# motor.net
KiCad netlist of a schematic drawn in Altium Designer
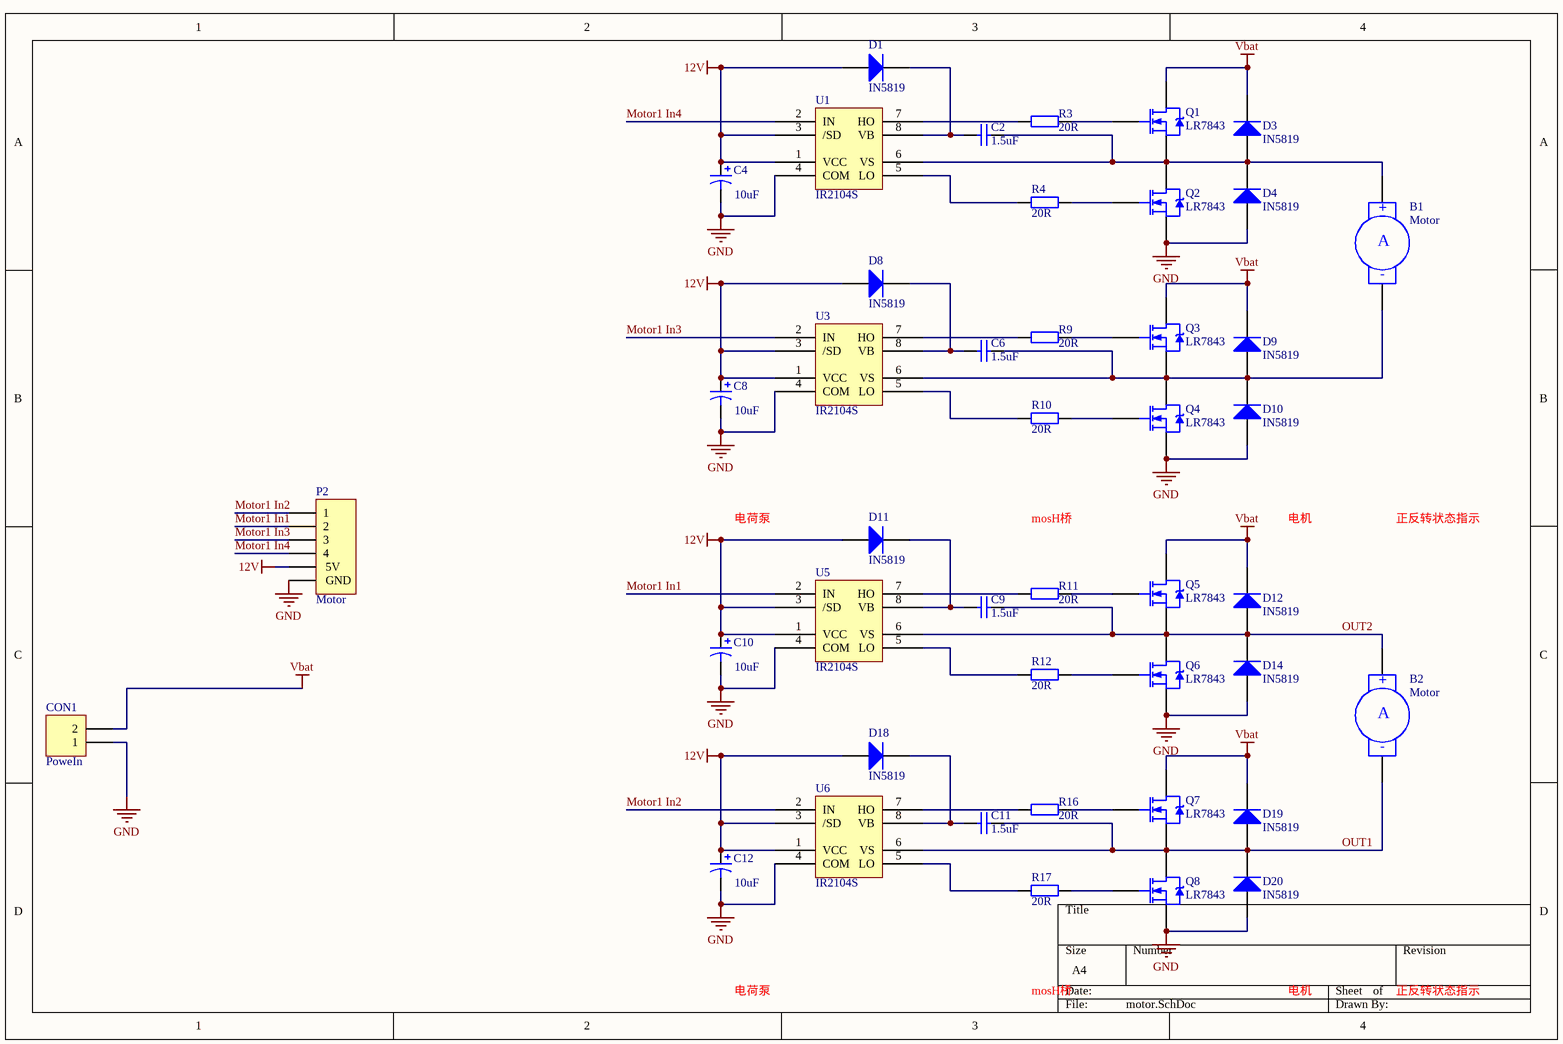
[diagram p0: motor.SchDoc]

(export (version "E")
  (design (tool "Eeschema 10.0.6"))
  (components
    (comp (ref "B1")
      (value "Motor")
      (footprint "KF301-2P")
      (description "Servo Motor")
      (fields (field (name "PUBLISHER") "Altium Limited"))
      (libsource (lib "Miscellaneous Devices") (part "Motor Servo"))
    )
    (comp (ref "B2")
      (value "Motor")
      (footprint "KF301-2P")
      (description "Servo Motor")
      (fields (field (name "PUBLISHER") "Altium Limited"))
      (libsource (lib "Miscellaneous Devices") (part "Motor Servo"))
    )
    (comp (ref "C2")
      (value "1.5uF")
      (footprint "0805(2012)")
      (description "Capacitor (Semiconductor SIM Model)")
      (fields (field (name "PUBLISHER") "Altium Limited"))
      (libsource (lib "Miscellaneous Devices") (part "Cap Semi"))
    )
    (comp (ref "C4")
      (value "10uF")
      (footprint "0805(2012)")
      (description "Polarized Capacitor (Surface Mount)")
      (fields (field (name "PUBLISHER") "Altium Limited"))
      (libsource (lib "Miscellaneous Devices") (part "Cap Pol3"))
    )
    (comp (ref "C6")
      (value "1.5uF")
      (footprint "0805(2012)")
      (description "Capacitor (Semiconductor SIM Model)")
      (fields (field (name "PUBLISHER") "Altium Limited"))
      (libsource (lib "Miscellaneous Devices") (part "Cap Semi"))
    )
    (comp (ref "C8")
      (value "10uF")
      (footprint "0805(2012)")
      (description "Polarized Capacitor (Surface Mount)")
      (fields (field (name "PUBLISHER") "Altium Limited"))
      (libsource (lib "Miscellaneous Devices") (part "Cap Pol3"))
    )
    (comp (ref "C9")
      (value "1.5uF")
      (footprint "0805(2012)")
      (description "Capacitor (Semiconductor SIM Model)")
      (fields (field (name "PUBLISHER") "Altium Limited"))
      (libsource (lib "Miscellaneous Devices") (part "Cap Semi"))
    )
    (comp (ref "C10")
      (value "10uF")
      (footprint "0805(2012)")
      (description "Polarized Capacitor (Surface Mount)")
      (fields (field (name "PUBLISHER") "Altium Limited"))
      (libsource (lib "Miscellaneous Devices") (part "Cap Pol3"))
    )
    (comp (ref "C11")
      (value "1.5uF")
      (footprint "0805(2012)")
      (description "Capacitor (Semiconductor SIM Model)")
      (fields (field (name "PUBLISHER") "Altium Limited"))
      (libsource (lib "Miscellaneous Devices") (part "Cap Semi"))
    )
    (comp (ref "C12")
      (value "10uF")
      (footprint "0805(2012)")
      (description "Polarized Capacitor (Surface Mount)")
      (fields (field (name "PUBLISHER") "Altium Limited"))
      (libsource (lib "Miscellaneous Devices") (part "Cap Pol3"))
    )
    (comp (ref "CON1")
      (value "PoweIn")
      (footprint "POWER")
      (description "Header, 2-Pin")
      (fields (field (name "PUBLISHER") "Altium Limited"))
      (libsource (lib "Miscellaneous Connectors") (part "Header 2"))
    )
    (comp (ref "D1")
      (value "IN5819")
      (footprint "1206(3216)")
      (description "Default Diode")
      (fields (field (name "PUBLISHER") "Altium Limited"))
      (libsource (lib "Miscellaneous Devices") (part "Diode"))
    )
    (comp (ref "D3")
      (value "IN5819")
      (footprint "1206(3216)")
      (description "Default Diode")
      (fields (field (name "PUBLISHER") "Altium Limited"))
      (libsource (lib "Miscellaneous Devices") (part "Diode"))
    )
    (comp (ref "D4")
      (value "IN5819")
      (footprint "1206(3216)")
      (description "Default Diode")
      (fields (field (name "PUBLISHER") "Altium Limited"))
      (libsource (lib "Miscellaneous Devices") (part "Diode"))
    )
    (comp (ref "D8")
      (value "IN5819")
      (footprint "1206(3216)")
      (description "Default Diode")
      (fields (field (name "PUBLISHER") "Altium Limited"))
      (libsource (lib "Miscellaneous Devices") (part "Diode"))
    )
    (comp (ref "D9")
      (value "IN5819")
      (footprint "1206(3216)")
      (description "Default Diode")
      (fields (field (name "PUBLISHER") "Altium Limited"))
      (libsource (lib "Miscellaneous Devices") (part "Diode"))
    )
    (comp (ref "D10")
      (value "IN5819")
      (footprint "1206(3216)")
      (description "Default Diode")
      (fields (field (name "PUBLISHER") "Altium Limited"))
      (libsource (lib "Miscellaneous Devices") (part "Diode"))
    )
    (comp (ref "D11")
      (value "IN5819")
      (footprint "1206(3216)")
      (description "Default Diode")
      (fields (field (name "PUBLISHER") "Altium Limited"))
      (libsource (lib "Miscellaneous Devices") (part "Diode"))
    )
    (comp (ref "D12")
      (value "IN5819")
      (footprint "1206(3216)")
      (description "Default Diode")
      (fields (field (name "PUBLISHER") "Altium Limited"))
      (libsource (lib "Miscellaneous Devices") (part "Diode"))
    )
    (comp (ref "D14")
      (value "IN5819")
      (footprint "1206(3216)")
      (description "Default Diode")
      (fields (field (name "PUBLISHER") "Altium Limited"))
      (libsource (lib "Miscellaneous Devices") (part "Diode"))
    )
    (comp (ref "D18")
      (value "IN5819")
      (footprint "1206(3216)")
      (description "Default Diode")
      (fields (field (name "PUBLISHER") "Altium Limited"))
      (libsource (lib "Miscellaneous Devices") (part "Diode"))
    )
    (comp (ref "D19")
      (value "IN5819")
      (footprint "1206(3216)")
      (description "Default Diode")
      (fields (field (name "PUBLISHER") "Altium Limited"))
      (libsource (lib "Miscellaneous Devices") (part "Diode"))
    )
    (comp (ref "D20")
      (value "IN5819")
      (footprint "1206(3216)")
      (description "Default Diode")
      (fields (field (name "PUBLISHER") "Altium Limited"))
      (libsource (lib "Miscellaneous Devices") (part "Diode"))
    )
    (comp (ref "P2") (value "Motor") (footprint "HDR1X6") (libsource (lib "主控板原理图") (part "Motor")))
    (comp (ref "Q1")
      (value "LR7843")
      (footprint "LR7843")
      (description "N-Channel Power MOSFET")
      (fields (field (name "PUBLISHER") "Altium Limited"))
      (libsource (lib "Miscellaneous Devices") (part "NMOS-2"))
    )
    (comp (ref "Q2")
      (value "LR7843")
      (footprint "LR7843")
      (description "N-Channel Power MOSFET")
      (fields (field (name "PUBLISHER") "Altium Limited"))
      (libsource (lib "Miscellaneous Devices") (part "NMOS-2"))
    )
    (comp (ref "Q3")
      (value "LR7843")
      (footprint "LR7843")
      (description "N-Channel Power MOSFET")
      (fields (field (name "PUBLISHER") "Altium Limited"))
      (libsource (lib "Miscellaneous Devices") (part "NMOS-2"))
    )
    (comp (ref "Q4")
      (value "LR7843")
      (footprint "LR7843")
      (description "N-Channel Power MOSFET")
      (fields (field (name "PUBLISHER") "Altium Limited"))
      (libsource (lib "Miscellaneous Devices") (part "NMOS-2"))
    )
    (comp (ref "Q5")
      (value "LR7843")
      (footprint "LR7843")
      (description "N-Channel Power MOSFET")
      (fields (field (name "PUBLISHER") "Altium Limited"))
      (libsource (lib "Miscellaneous Devices") (part "NMOS-2"))
    )
    (comp (ref "Q6")
      (value "LR7843")
      (footprint "LR7843")
      (description "N-Channel Power MOSFET")
      (fields (field (name "PUBLISHER") "Altium Limited"))
      (libsource (lib "Miscellaneous Devices") (part "NMOS-2"))
    )
    (comp (ref "Q7")
      (value "LR7843")
      (footprint "LR7843")
      (description "N-Channel Power MOSFET")
      (fields (field (name "PUBLISHER") "Altium Limited"))
      (libsource (lib "Miscellaneous Devices") (part "NMOS-2"))
    )
    (comp (ref "Q8")
      (value "LR7843")
      (footprint "LR7843")
      (description "N-Channel Power MOSFET")
      (fields (field (name "PUBLISHER") "Altium Limited"))
      (libsource (lib "Miscellaneous Devices") (part "NMOS-2"))
    )
    (comp (ref "R3")
      (value "20R")
      (footprint "0603")
      (description "Resistor")
      (fields (field (name "PUBLISHER") "Altium Limited"))
      (libsource (lib "Miscellaneous Devices") (part "Res2"))
    )
    (comp (ref "R4")
      (value "20R")
      (footprint "0603")
      (description "Resistor")
      (fields (field (name "PUBLISHER") "Altium Limited"))
      (libsource (lib "Miscellaneous Devices") (part "Res2"))
    )
    (comp (ref "R9")
      (value "20R")
      (footprint "0603")
      (description "Resistor")
      (fields (field (name "PUBLISHER") "Altium Limited"))
      (libsource (lib "Miscellaneous Devices") (part "Res2"))
    )
    (comp (ref "R10")
      (value "20R")
      (footprint "0603")
      (description "Resistor")
      (fields (field (name "PUBLISHER") "Altium Limited"))
      (libsource (lib "Miscellaneous Devices") (part "Res2"))
    )
    (comp (ref "R11")
      (value "20R")
      (footprint "0603")
      (description "Resistor")
      (fields (field (name "PUBLISHER") "Altium Limited"))
      (libsource (lib "Miscellaneous Devices") (part "Res2"))
    )
    (comp (ref "R12")
      (value "20R")
      (footprint "0603")
      (description "Resistor")
      (fields (field (name "PUBLISHER") "Altium Limited"))
      (libsource (lib "Miscellaneous Devices") (part "Res2"))
    )
    (comp (ref "R16")
      (value "20R")
      (footprint "0603")
      (description "Resistor")
      (fields (field (name "PUBLISHER") "Altium Limited"))
      (libsource (lib "Miscellaneous Devices") (part "Res2"))
    )
    (comp (ref "R17")
      (value "20R")
      (footprint "0603")
      (description "Resistor")
      (fields (field (name "PUBLISHER") "Altium Limited"))
      (libsource (lib "Miscellaneous Devices") (part "Res2"))
    )
    (comp (ref "U1") (value "IR2104S") (footprint "IR2104S") (libsource (lib "LY") (part "IR2104S")))
    (comp (ref "U3") (value "IR2104S") (footprint "IR2104S") (libsource (lib "LY") (part "IR2104S")))
    (comp (ref "U5") (value "IR2104S") (footprint "IR2104S") (libsource (lib "LY") (part "IR2104S")))
    (comp (ref "U6") (value "IR2104S") (footprint "IR2104S") (libsource (lib "LY") (part "IR2104S")))
  )
  (nets
    (net (code "1") (name "/Motor1 In1") (class "Default")
      (node (ref "P2") (pin "2") (pinfunction "2_2") (pintype "passive"))
      (node (ref "U5") (pin "2") (pinfunction "IN_2") (pintype "passive"))
    )
    (net (code "2") (name "/Motor1 In2") (class "Default")
      (node (ref "P2") (pin "1") (pinfunction "1_1") (pintype "passive"))
      (node (ref "U6") (pin "2") (pinfunction "IN_2") (pintype "passive"))
    )
    (net (code "3") (name "/Motor1 In3") (class "Default")
      (node (ref "P2") (pin "3") (pinfunction "3_3") (pintype "passive"))
      (node (ref "U3") (pin "2") (pinfunction "IN_2") (pintype "passive"))
    )
    (net (code "4") (name "/Motor1 In4") (class "Default")
      (node (ref "P2") (pin "4") (pinfunction "4_4") (pintype "passive"))
      (node (ref "U1") (pin "2") (pinfunction "IN_2") (pintype "passive"))
    )
    (net (code "5") (name "/OUT1") (class "Default")
      (node (ref "B2") (pin "2") (pinfunction "-_2") (pintype "passive"))
      (node (ref "C11") (pin "2") (pinfunction "2_2") (pintype "passive"))
      (node (ref "D19") (pin "1") (pinfunction "A_1") (pintype "passive"))
      (node (ref "D20") (pin "2") (pinfunction "K_2") (pintype "passive"))
      (node (ref "Q7") (pin "3") (pinfunction "S_3") (pintype "passive"))
      (node (ref "Q8") (pin "2") (pinfunction "D_2") (pintype "passive"))
      (node (ref "U6") (pin "6") (pinfunction "VS_6") (pintype "passive"))
    )
    (net (code "6") (name "/OUT2") (class "Default")
      (node (ref "B2") (pin "1") (pinfunction "+_1") (pintype "passive"))
      (node (ref "C9") (pin "2") (pinfunction "2_2") (pintype "passive"))
      (node (ref "D12") (pin "1") (pinfunction "A_1") (pintype "passive"))
      (node (ref "D14") (pin "2") (pinfunction "K_2") (pintype "passive"))
      (node (ref "Q5") (pin "3") (pinfunction "S_3") (pintype "passive"))
      (node (ref "Q6") (pin "2") (pinfunction "D_2") (pintype "passive"))
      (node (ref "U5") (pin "6") (pinfunction "VS_6") (pintype "passive"))
    )
    (net (code "7") (name "12V") (class "Default")
      (node (ref "C10") (pin "1") (pinfunction "1_1") (pintype "passive"))
      (node (ref "C12") (pin "1") (pinfunction "1_1") (pintype "passive"))
      (node (ref "C4") (pin "1") (pinfunction "1_1") (pintype "passive"))
      (node (ref "C8") (pin "1") (pinfunction "1_1") (pintype "passive"))
      (node (ref "D1") (pin "1") (pinfunction "A_1") (pintype "passive"))
      (node (ref "D11") (pin "1") (pinfunction "A_1") (pintype "passive"))
      (node (ref "D18") (pin "1") (pinfunction "A_1") (pintype "passive"))
      (node (ref "D8") (pin "1") (pinfunction "A_1") (pintype "passive"))
      (node (ref "P2") (pin "5") (pinfunction "5V_5") (pintype "passive"))
      (node (ref "U1") (pin "1") (pinfunction "VCC_1") (pintype "passive"))
      (node (ref "U1") (pin "3") (pinfunction "/SD_3") (pintype "passive"))
      (node (ref "U3") (pin "1") (pinfunction "VCC_1") (pintype "passive"))
      (node (ref "U3") (pin "3") (pinfunction "/SD_3") (pintype "passive"))
      (node (ref "U5") (pin "1") (pinfunction "VCC_1") (pintype "passive"))
      (node (ref "U5") (pin "3") (pinfunction "/SD_3") (pintype "passive"))
      (node (ref "U6") (pin "1") (pinfunction "VCC_1") (pintype "passive"))
      (node (ref "U6") (pin "3") (pinfunction "/SD_3") (pintype "passive"))
    )
    (net (code "8") (name "GND") (class "Default")
      (node (ref "C10") (pin "2") (pinfunction "2_2") (pintype "passive"))
      (node (ref "C12") (pin "2") (pinfunction "2_2") (pintype "passive"))
      (node (ref "C4") (pin "2") (pinfunction "2_2") (pintype "passive"))
      (node (ref "C8") (pin "2") (pinfunction "2_2") (pintype "passive"))
      (node (ref "CON1") (pin "1") (pinfunction "1_1") (pintype "passive"))
      (node (ref "D10") (pin "1") (pinfunction "A_1") (pintype "passive"))
      (node (ref "D14") (pin "1") (pinfunction "A_1") (pintype "passive"))
      (node (ref "D20") (pin "1") (pinfunction "A_1") (pintype "passive"))
      (node (ref "D4") (pin "1") (pinfunction "A_1") (pintype "passive"))
      (node (ref "P2") (pin "6") (pinfunction "GND_6") (pintype "passive"))
      (node (ref "Q2") (pin "3") (pinfunction "S_3") (pintype "passive"))
      (node (ref "Q4") (pin "3") (pinfunction "S_3") (pintype "passive"))
      (node (ref "Q6") (pin "3") (pinfunction "S_3") (pintype "passive"))
      (node (ref "Q8") (pin "3") (pinfunction "S_3") (pintype "passive"))
      (node (ref "U1") (pin "4") (pinfunction "COM_4") (pintype "passive"))
      (node (ref "U3") (pin "4") (pinfunction "COM_4") (pintype "passive"))
      (node (ref "U5") (pin "4") (pinfunction "COM_4") (pintype "passive"))
      (node (ref "U6") (pin "4") (pinfunction "COM_4") (pintype "passive"))
    )
    (net (code "9") (name "Net-(B1-+)") (class "Default")
      (node (ref "B1") (pin "1") (pinfunction "+_1") (pintype "passive"))
      (node (ref "C2") (pin "2") (pinfunction "2_2") (pintype "passive"))
      (node (ref "D3") (pin "1") (pinfunction "A_1") (pintype "passive"))
      (node (ref "D4") (pin "2") (pinfunction "K_2") (pintype "passive"))
      (node (ref "Q1") (pin "3") (pinfunction "S_3") (pintype "passive"))
      (node (ref "Q2") (pin "2") (pinfunction "D_2") (pintype "passive"))
      (node (ref "U1") (pin "6") (pinfunction "VS_6") (pintype "passive"))
    )
    (net (code "10") (name "Net-(B1--)") (class "Default")
      (node (ref "B1") (pin "2") (pinfunction "-_2") (pintype "passive"))
      (node (ref "C6") (pin "2") (pinfunction "2_2") (pintype "passive"))
      (node (ref "D10") (pin "2") (pinfunction "K_2") (pintype "passive"))
      (node (ref "D9") (pin "1") (pinfunction "A_1") (pintype "passive"))
      (node (ref "Q3") (pin "3") (pinfunction "S_3") (pintype "passive"))
      (node (ref "Q4") (pin "2") (pinfunction "D_2") (pintype "passive"))
      (node (ref "U3") (pin "6") (pinfunction "VS_6") (pintype "passive"))
    )
    (net (code "11") (name "Net-(D1-K)") (class "Default")
      (node (ref "C2") (pin "1") (pinfunction "1_1") (pintype "passive"))
      (node (ref "D1") (pin "2") (pinfunction "K_2") (pintype "passive"))
      (node (ref "U1") (pin "8") (pinfunction "VB_8") (pintype "passive"))
    )
    (net (code "12") (name "Net-(D8-K)") (class "Default")
      (node (ref "C6") (pin "1") (pinfunction "1_1") (pintype "passive"))
      (node (ref "D8") (pin "2") (pinfunction "K_2") (pintype "passive"))
      (node (ref "U3") (pin "8") (pinfunction "VB_8") (pintype "passive"))
    )
    (net (code "13") (name "Net-(D11-K)") (class "Default")
      (node (ref "C9") (pin "1") (pinfunction "1_1") (pintype "passive"))
      (node (ref "D11") (pin "2") (pinfunction "K_2") (pintype "passive"))
      (node (ref "U5") (pin "8") (pinfunction "VB_8") (pintype "passive"))
    )
    (net (code "14") (name "Net-(D18-K)") (class "Default")
      (node (ref "C11") (pin "1") (pinfunction "1_1") (pintype "passive"))
      (node (ref "D18") (pin "2") (pinfunction "K_2") (pintype "passive"))
      (node (ref "U6") (pin "8") (pinfunction "VB_8") (pintype "passive"))
    )
    (net (code "15") (name "Net-(Q1-G)") (class "Default")
      (node (ref "Q1") (pin "1") (pinfunction "G_1") (pintype "passive"))
      (node (ref "R3") (pin "2") (pinfunction "2_2") (pintype "passive"))
    )
    (net (code "16") (name "Net-(Q2-G)") (class "Default")
      (node (ref "Q2") (pin "1") (pinfunction "G_1") (pintype "passive"))
      (node (ref "R4") (pin "2") (pinfunction "2_2") (pintype "passive"))
    )
    (net (code "17") (name "Net-(Q3-G)") (class "Default")
      (node (ref "Q3") (pin "1") (pinfunction "G_1") (pintype "passive"))
      (node (ref "R9") (pin "2") (pinfunction "2_2") (pintype "passive"))
    )
    (net (code "18") (name "Net-(Q4-G)") (class "Default")
      (node (ref "Q4") (pin "1") (pinfunction "G_1") (pintype "passive"))
      (node (ref "R10") (pin "2") (pinfunction "2_2") (pintype "passive"))
    )
    (net (code "19") (name "Net-(Q5-G)") (class "Default")
      (node (ref "Q5") (pin "1") (pinfunction "G_1") (pintype "passive"))
      (node (ref "R11") (pin "2") (pinfunction "2_2") (pintype "passive"))
    )
    (net (code "20") (name "Net-(Q6-G)") (class "Default")
      (node (ref "Q6") (pin "1") (pinfunction "G_1") (pintype "passive"))
      (node (ref "R12") (pin "2") (pinfunction "2_2") (pintype "passive"))
    )
    (net (code "21") (name "Net-(Q7-G)") (class "Default")
      (node (ref "Q7") (pin "1") (pinfunction "G_1") (pintype "passive"))
      (node (ref "R16") (pin "2") (pinfunction "2_2") (pintype "passive"))
    )
    (net (code "22") (name "Net-(Q8-G)") (class "Default")
      (node (ref "Q8") (pin "1") (pinfunction "G_1") (pintype "passive"))
      (node (ref "R17") (pin "2") (pinfunction "2_2") (pintype "passive"))
    )
    (net (code "23") (name "Net-(U1-HO)") (class "Default")
      (node (ref "R3") (pin "1") (pinfunction "1_1") (pintype "passive"))
      (node (ref "U1") (pin "7") (pinfunction "HO_7") (pintype "passive"))
    )
    (net (code "24") (name "Net-(U1-LO)") (class "Default")
      (node (ref "R4") (pin "1") (pinfunction "1_1") (pintype "passive"))
      (node (ref "U1") (pin "5") (pinfunction "LO_5") (pintype "passive"))
    )
    (net (code "25") (name "Net-(U3-HO)") (class "Default")
      (node (ref "R9") (pin "1") (pinfunction "1_1") (pintype "passive"))
      (node (ref "U3") (pin "7") (pinfunction "HO_7") (pintype "passive"))
    )
    (net (code "26") (name "Net-(U3-LO)") (class "Default")
      (node (ref "R10") (pin "1") (pinfunction "1_1") (pintype "passive"))
      (node (ref "U3") (pin "5") (pinfunction "LO_5") (pintype "passive"))
    )
    (net (code "27") (name "Net-(U5-HO)") (class "Default")
      (node (ref "R11") (pin "1") (pinfunction "1_1") (pintype "passive"))
      (node (ref "U5") (pin "7") (pinfunction "HO_7") (pintype "passive"))
    )
    (net (code "28") (name "Net-(U5-LO)") (class "Default")
      (node (ref "R12") (pin "1") (pinfunction "1_1") (pintype "passive"))
      (node (ref "U5") (pin "5") (pinfunction "LO_5") (pintype "passive"))
    )
    (net (code "29") (name "Net-(U6-HO)") (class "Default")
      (node (ref "R16") (pin "1") (pinfunction "1_1") (pintype "passive"))
      (node (ref "U6") (pin "7") (pinfunction "HO_7") (pintype "passive"))
    )
    (net (code "30") (name "Net-(U6-LO)") (class "Default")
      (node (ref "R17") (pin "1") (pinfunction "1_1") (pintype "passive"))
      (node (ref "U6") (pin "5") (pinfunction "LO_5") (pintype "passive"))
    )
    (net (code "31") (name "Vbat") (class "Default")
      (node (ref "CON1") (pin "2") (pinfunction "2_2") (pintype "passive"))
      (node (ref "D12") (pin "2") (pinfunction "K_2") (pintype "passive"))
      (node (ref "D19") (pin "2") (pinfunction "K_2") (pintype "passive"))
      (node (ref "D3") (pin "2") (pinfunction "K_2") (pintype "passive"))
      (node (ref "D9") (pin "2") (pinfunction "K_2") (pintype "passive"))
      (node (ref "Q1") (pin "2") (pinfunction "D_2") (pintype "passive"))
      (node (ref "Q3") (pin "2") (pinfunction "D_2") (pintype "passive"))
      (node (ref "Q5") (pin "2") (pinfunction "D_2") (pintype "passive"))
      (node (ref "Q7") (pin "2") (pinfunction "D_2") (pintype "passive"))
    )
  )
)
